# currentSens.net
KiCad netlist of a schematic drawn in EAGLE
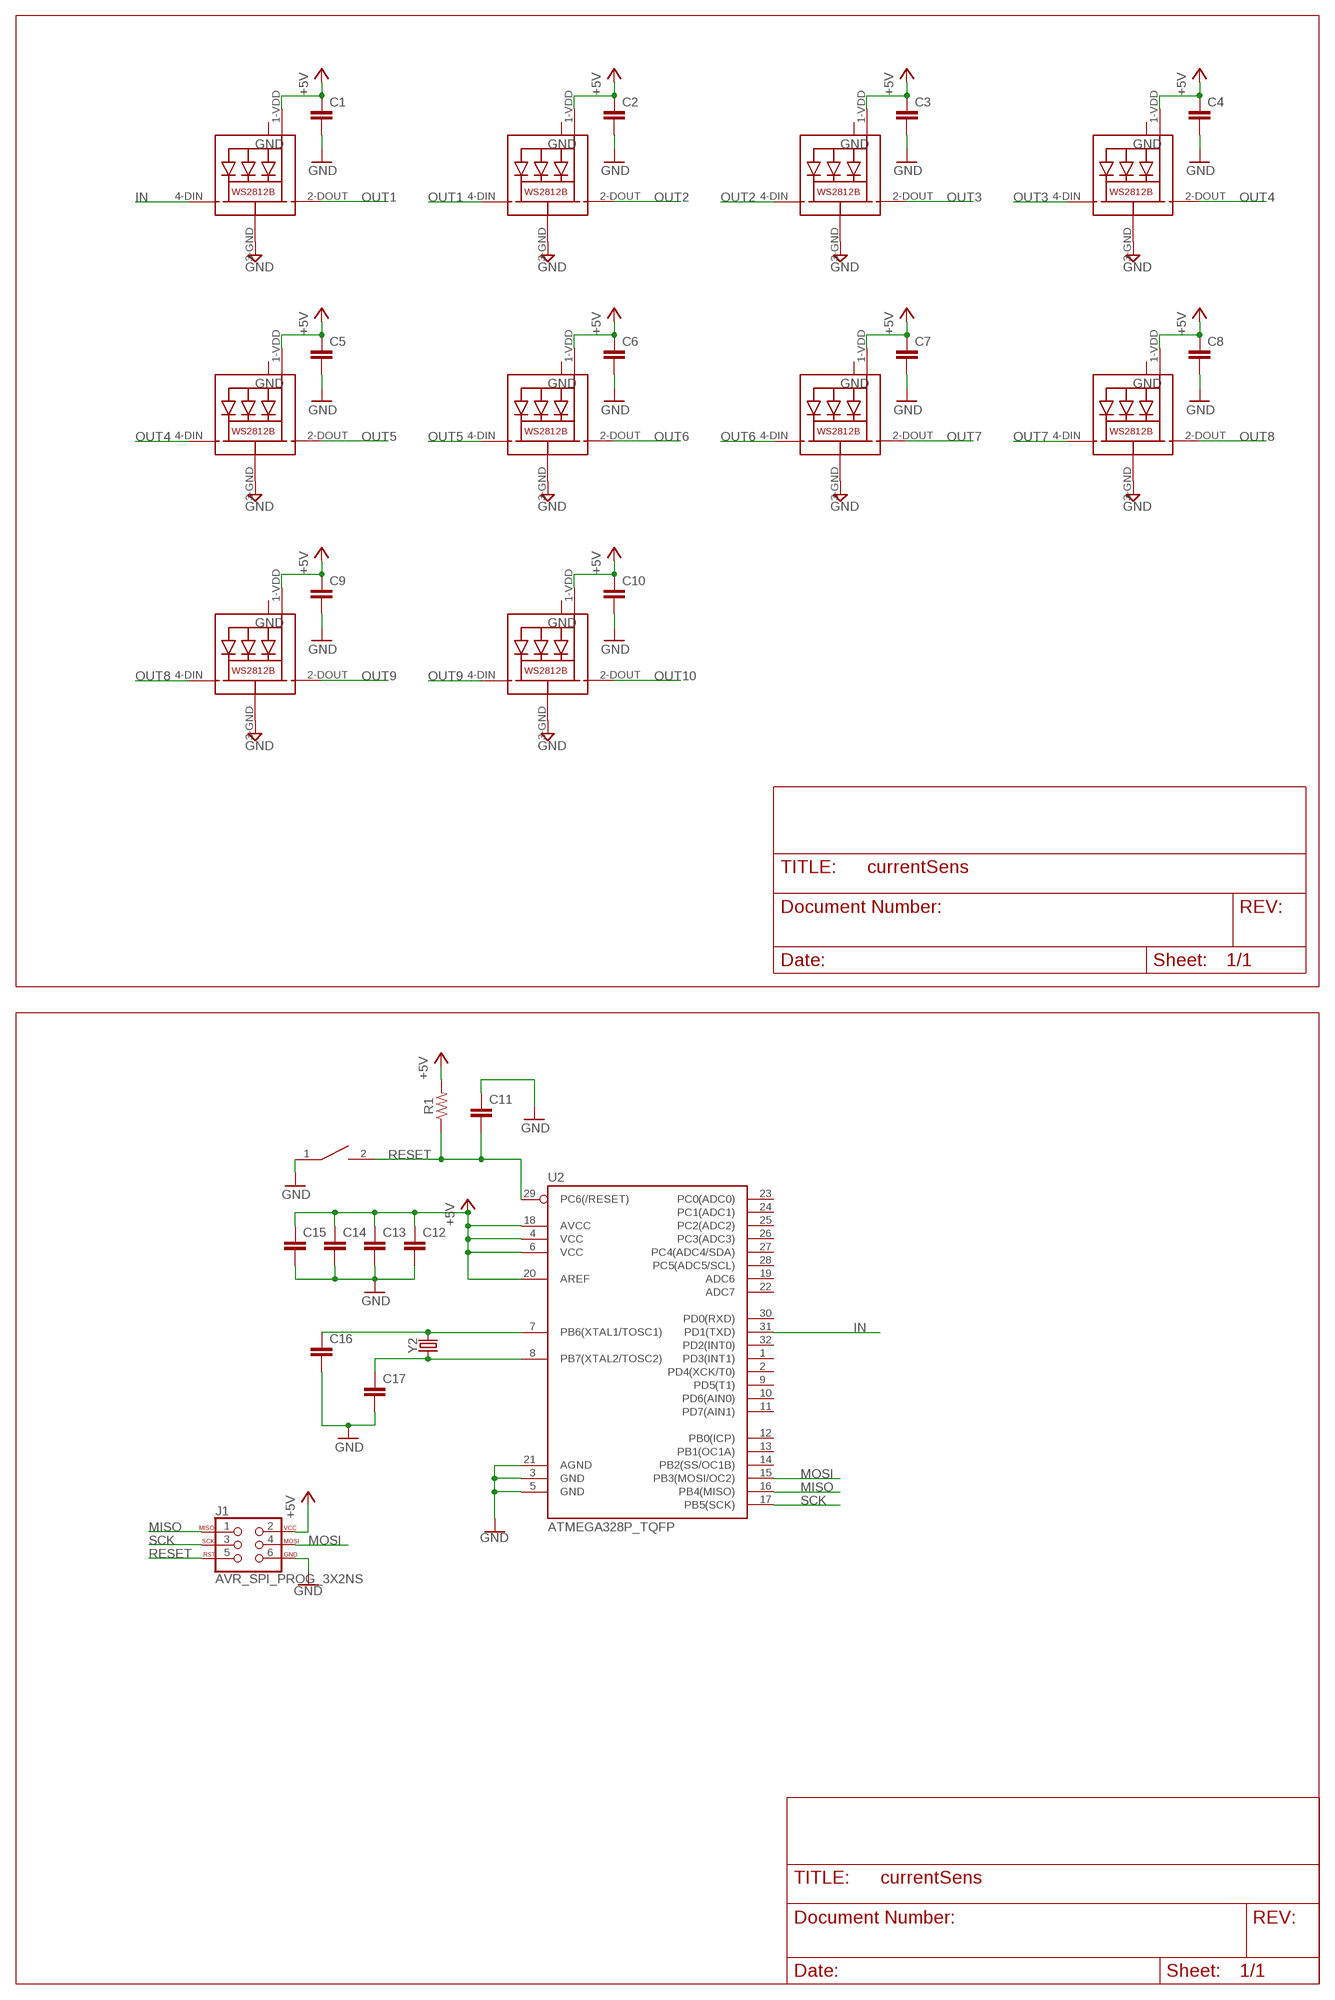
[diagram p0: schematic, sheet 1]

(export (version "E")
  (design (tool "Eeschema 10.0.6"))
  (components
    (comp (ref "BOOT")
      (value "SWITCH")
      (footprint "eagle-import:SW_2512")
      (libsource (lib "eagle-import") (part "SWITCH"))
    )
    (comp (ref "C1")
      (value "C-EUC0603")
      (footprint "eagle-import:C0603")
      (libsource (lib "eagle-import") (part "C-EUC0603"))
    )
    (comp (ref "C2")
      (value "C-EUC0603")
      (footprint "eagle-import:C0603")
      (libsource (lib "eagle-import") (part "C-EUC0603"))
    )
    (comp (ref "C3")
      (value "C-EUC0603")
      (footprint "eagle-import:C0603")
      (libsource (lib "eagle-import") (part "C-EUC0603"))
    )
    (comp (ref "C4")
      (value "C-EUC0603")
      (footprint "eagle-import:C0603")
      (libsource (lib "eagle-import") (part "C-EUC0603"))
    )
    (comp (ref "C5")
      (value "C-EUC0603")
      (footprint "eagle-import:C0603")
      (libsource (lib "eagle-import") (part "C-EUC0603"))
    )
    (comp (ref "C6")
      (value "C-EUC0603")
      (footprint "eagle-import:C0603")
      (libsource (lib "eagle-import") (part "C-EUC0603"))
    )
    (comp (ref "C7")
      (value "C-EUC0603")
      (footprint "eagle-import:C0603")
      (libsource (lib "eagle-import") (part "C-EUC0603"))
    )
    (comp (ref "C8")
      (value "C-EUC0603")
      (footprint "eagle-import:C0603")
      (libsource (lib "eagle-import") (part "C-EUC0603"))
    )
    (comp (ref "C9")
      (value "C-EUC0603")
      (footprint "eagle-import:C0603")
      (libsource (lib "eagle-import") (part "C-EUC0603"))
    )
    (comp (ref "C10")
      (value "C-EUC0603")
      (footprint "eagle-import:C0603")
      (libsource (lib "eagle-import") (part "C-EUC0603"))
    )
    (comp (ref "C11")
      (value "C-EUC0603")
      (footprint "eagle-import:C0603")
      (libsource (lib "eagle-import") (part "C-EUC0603"))
    )
    (comp (ref "C12")
      (value "C-EUC0603")
      (footprint "eagle-import:C0603")
      (libsource (lib "eagle-import") (part "C-EUC0603"))
    )
    (comp (ref "C13")
      (value "C-EUC0603")
      (footprint "eagle-import:C0603")
      (libsource (lib "eagle-import") (part "C-EUC0603"))
    )
    (comp (ref "C14")
      (value "C-EUC0603")
      (footprint "eagle-import:C0603")
      (libsource (lib "eagle-import") (part "C-EUC0603"))
    )
    (comp (ref "C15")
      (value "C-EUC0603")
      (footprint "eagle-import:C0603")
      (libsource (lib "eagle-import") (part "C-EUC0603"))
    )
    (comp (ref "C16")
      (value "C-EUC0603")
      (footprint "eagle-import:C0603")
      (libsource (lib "eagle-import") (part "C-EUC0603"))
    )
    (comp (ref "C17")
      (value "C-EUC0603")
      (footprint "eagle-import:C0603")
      (libsource (lib "eagle-import") (part "C-EUC0603"))
    )
    (comp (ref "J1")
      (value "AVR_SPI_PROG_3X2NS")
      (footprint "eagle-import:2X3-NS")
      (libsource (lib "eagle-import") (part "AVR_SPI_PROG_3X2NS"))
    )
    (comp (ref "LED1")
      (value "WS2812B5050")
      (footprint "eagle-import:WS2812B")
      (libsource (lib "eagle-import") (part "WS2812B5050"))
    )
    (comp (ref "LED2")
      (value "WS2812B5050")
      (footprint "eagle-import:WS2812B")
      (libsource (lib "eagle-import") (part "WS2812B5050"))
    )
    (comp (ref "LED3")
      (value "WS2812B5050")
      (footprint "eagle-import:WS2812B")
      (libsource (lib "eagle-import") (part "WS2812B5050"))
    )
    (comp (ref "LED4")
      (value "WS2812B5050")
      (footprint "eagle-import:WS2812B")
      (libsource (lib "eagle-import") (part "WS2812B5050"))
    )
    (comp (ref "LED5")
      (value "WS2812B5050")
      (footprint "eagle-import:WS2812B")
      (libsource (lib "eagle-import") (part "WS2812B5050"))
    )
    (comp (ref "LED6")
      (value "WS2812B5050")
      (footprint "eagle-import:WS2812B")
      (libsource (lib "eagle-import") (part "WS2812B5050"))
    )
    (comp (ref "LED7")
      (value "WS2812B5050")
      (footprint "eagle-import:WS2812B")
      (libsource (lib "eagle-import") (part "WS2812B5050"))
    )
    (comp (ref "LED8")
      (value "WS2812B5050")
      (footprint "eagle-import:WS2812B")
      (libsource (lib "eagle-import") (part "WS2812B5050"))
    )
    (comp (ref "LED9")
      (value "WS2812B5050")
      (footprint "eagle-import:WS2812B")
      (libsource (lib "eagle-import") (part "WS2812B5050"))
    )
    (comp (ref "LED10")
      (value "WS2812B5050")
      (footprint "eagle-import:WS2812B")
      (libsource (lib "eagle-import") (part "WS2812B5050"))
    )
    (comp (ref "R1")
      (value "RESISTOR0603")
      (footprint "eagle-import:0603")
      (libsource (lib "eagle-import") (part "RESISTOR0603"))
    )
    (comp (ref "U2")
      (value "ATMEGA328P_TQFP")
      (footprint "eagle-import:TQFP32-08")
      (libsource (lib "eagle-import") (part "ATMEGA328P_TQFP"))
    )
    (comp (ref "Y2")
      (value "CRYSTALPTH-HC49US")
      (footprint "eagle-import:HC49US")
      (libsource (lib "eagle-import") (part "CRYSTALPTH-HC49US"))
    )
  )
  (nets
    (net (code "1") (name "+5V") (class "Default")
      (node (ref "C1") (pin "1") (pinfunction "1_1") (pintype "passive"))
      (node (ref "C10") (pin "1") (pinfunction "1_1") (pintype "passive"))
      (node (ref "C12") (pin "1") (pinfunction "1_1") (pintype "passive"))
      (node (ref "C13") (pin "1") (pinfunction "1_1") (pintype "passive"))
      (node (ref "C14") (pin "1") (pinfunction "1_1") (pintype "passive"))
      (node (ref "C15") (pin "1") (pinfunction "1_1") (pintype "passive"))
      (node (ref "C2") (pin "1") (pinfunction "1_1") (pintype "passive"))
      (node (ref "C3") (pin "1") (pinfunction "1_1") (pintype "passive"))
      (node (ref "C4") (pin "1") (pinfunction "1_1") (pintype "passive"))
      (node (ref "C5") (pin "1") (pinfunction "1_1") (pintype "passive"))
      (node (ref "C6") (pin "1") (pinfunction "1_1") (pintype "passive"))
      (node (ref "C7") (pin "1") (pinfunction "1_1") (pintype "passive"))
      (node (ref "C8") (pin "1") (pinfunction "1_1") (pintype "passive"))
      (node (ref "C9") (pin "1") (pinfunction "1_1") (pintype "passive"))
      (node (ref "J1") (pin "2") (pinfunction "2_2") (pintype "passive"))
      (node (ref "LED1") (pin "1-VDD") (pinfunction "VDD_1-VDD") (pintype "power_in"))
      (node (ref "LED10") (pin "1-VDD") (pinfunction "VDD_1-VDD") (pintype "power_in"))
      (node (ref "LED2") (pin "1-VDD") (pinfunction "VDD_1-VDD") (pintype "power_in"))
      (node (ref "LED3") (pin "1-VDD") (pinfunction "VDD_1-VDD") (pintype "power_in"))
      (node (ref "LED4") (pin "1-VDD") (pinfunction "VDD_1-VDD") (pintype "power_in"))
      (node (ref "LED5") (pin "1-VDD") (pinfunction "VDD_1-VDD") (pintype "power_in"))
      (node (ref "LED6") (pin "1-VDD") (pinfunction "VDD_1-VDD") (pintype "power_in"))
      (node (ref "LED7") (pin "1-VDD") (pinfunction "VDD_1-VDD") (pintype "power_in"))
      (node (ref "LED8") (pin "1-VDD") (pinfunction "VDD_1-VDD") (pintype "power_in"))
      (node (ref "LED9") (pin "1-VDD") (pinfunction "VDD_1-VDD") (pintype "power_in"))
      (node (ref "R1") (pin "2") (pinfunction "2_2") (pintype "passive"))
      (node (ref "U2") (pin "18") (pinfunction "AVCC_18") (pintype "bidirectional"))
      (node (ref "U2") (pin "20") (pinfunction "AREF_20") (pintype "bidirectional"))
      (node (ref "U2") (pin "4") (pinfunction "VCC_4") (pintype "bidirectional"))
      (node (ref "U2") (pin "6") (pinfunction "VCC_6") (pintype "bidirectional"))
    )
    (net (code "2") (name "/IN") (class "Default")
      (node (ref "LED1") (pin "4-DIN") (pinfunction "DI_4-DIN") (pintype "input"))
      (node (ref "U2") (pin "31") (pinfunction "PD1(TXD)_31") (pintype "bidirectional"))
    )
    (net (code "3") (name "/MISO") (class "Default")
      (node (ref "J1") (pin "1") (pinfunction "1_1") (pintype "passive"))
      (node (ref "U2") (pin "16") (pinfunction "PB4(MISO)_16") (pintype "bidirectional"))
    )
    (net (code "4") (name "/MOSI") (class "Default")
      (node (ref "J1") (pin "4") (pinfunction "4_4") (pintype "passive"))
      (node (ref "U2") (pin "15") (pinfunction "PB3(MOSI/OC2)_15") (pintype "bidirectional"))
    )
    (net (code "5") (name "/OUT1") (class "Default")
      (node (ref "LED1") (pin "2-DOUT") (pinfunction "DO_2-DOUT") (pintype "output"))
      (node (ref "LED2") (pin "4-DIN") (pinfunction "DI_4-DIN") (pintype "input"))
    )
    (net (code "6") (name "/OUT2") (class "Default")
      (node (ref "LED2") (pin "2-DOUT") (pinfunction "DO_2-DOUT") (pintype "output"))
      (node (ref "LED3") (pin "4-DIN") (pinfunction "DI_4-DIN") (pintype "input"))
    )
    (net (code "7") (name "/OUT3") (class "Default")
      (node (ref "LED3") (pin "2-DOUT") (pinfunction "DO_2-DOUT") (pintype "output"))
      (node (ref "LED4") (pin "4-DIN") (pinfunction "DI_4-DIN") (pintype "input"))
    )
    (net (code "8") (name "/OUT4") (class "Default")
      (node (ref "LED4") (pin "2-DOUT") (pinfunction "DO_2-DOUT") (pintype "output"))
      (node (ref "LED5") (pin "4-DIN") (pinfunction "DI_4-DIN") (pintype "input"))
    )
    (net (code "9") (name "/OUT5") (class "Default")
      (node (ref "LED5") (pin "2-DOUT") (pinfunction "DO_2-DOUT") (pintype "output"))
      (node (ref "LED6") (pin "4-DIN") (pinfunction "DI_4-DIN") (pintype "input"))
    )
    (net (code "10") (name "/OUT6") (class "Default")
      (node (ref "LED6") (pin "2-DOUT") (pinfunction "DO_2-DOUT") (pintype "output"))
      (node (ref "LED7") (pin "4-DIN") (pinfunction "DI_4-DIN") (pintype "input"))
    )
    (net (code "11") (name "/OUT7") (class "Default")
      (node (ref "LED7") (pin "2-DOUT") (pinfunction "DO_2-DOUT") (pintype "output"))
      (node (ref "LED8") (pin "4-DIN") (pinfunction "DI_4-DIN") (pintype "input"))
    )
    (net (code "12") (name "/OUT8") (class "Default")
      (node (ref "LED8") (pin "2-DOUT") (pinfunction "DO_2-DOUT") (pintype "output"))
      (node (ref "LED9") (pin "4-DIN") (pinfunction "DI_4-DIN") (pintype "input"))
    )
    (net (code "13") (name "/OUT9") (class "Default")
      (node (ref "LED10") (pin "4-DIN") (pinfunction "DI_4-DIN") (pintype "input"))
      (node (ref "LED9") (pin "2-DOUT") (pinfunction "DO_2-DOUT") (pintype "output"))
    )
    (net (code "14") (name "/OUT10") (class "Default")
      (node (ref "LED10") (pin "2-DOUT") (pinfunction "DO_2-DOUT") (pintype "output"))
    )
    (net (code "15") (name "/RESET") (class "Default")
      (node (ref "BOOT") (pin "2") (pinfunction "P$2_2") (pintype "bidirectional"))
      (node (ref "C11") (pin "2") (pinfunction "2_2") (pintype "passive"))
      (node (ref "J1") (pin "5") (pinfunction "5_5") (pintype "passive"))
      (node (ref "R1") (pin "1") (pinfunction "1_1") (pintype "passive"))
      (node (ref "U2") (pin "29") (pinfunction "PC6(/RESET)_29") (pintype "bidirectional"))
    )
    (net (code "16") (name "/SCK") (class "Default")
      (node (ref "J1") (pin "3") (pinfunction "3_3") (pintype "passive"))
      (node (ref "U2") (pin "17") (pinfunction "PB5(SCK)_17") (pintype "bidirectional"))
    )
    (net (code "17") (name "GND") (class "Default")
      (node (ref "BOOT") (pin "1") (pinfunction "P$1_1") (pintype "bidirectional"))
      (node (ref "C1") (pin "2") (pinfunction "2_2") (pintype "passive"))
      (node (ref "C10") (pin "2") (pinfunction "2_2") (pintype "passive"))
      (node (ref "C11") (pin "1") (pinfunction "1_1") (pintype "passive"))
      (node (ref "C12") (pin "2") (pinfunction "2_2") (pintype "passive"))
      (node (ref "C13") (pin "2") (pinfunction "2_2") (pintype "passive"))
      (node (ref "C14") (pin "2") (pinfunction "2_2") (pintype "passive"))
      (node (ref "C15") (pin "2") (pinfunction "2_2") (pintype "passive"))
      (node (ref "C16") (pin "2") (pinfunction "2_2") (pintype "passive"))
      (node (ref "C17") (pin "2") (pinfunction "2_2") (pintype "passive"))
      (node (ref "C2") (pin "2") (pinfunction "2_2") (pintype "passive"))
      (node (ref "C3") (pin "2") (pinfunction "2_2") (pintype "passive"))
      (node (ref "C4") (pin "2") (pinfunction "2_2") (pintype "passive"))
      (node (ref "C5") (pin "2") (pinfunction "2_2") (pintype "passive"))
      (node (ref "C6") (pin "2") (pinfunction "2_2") (pintype "passive"))
      (node (ref "C7") (pin "2") (pinfunction "2_2") (pintype "passive"))
      (node (ref "C8") (pin "2") (pinfunction "2_2") (pintype "passive"))
      (node (ref "C9") (pin "2") (pinfunction "2_2") (pintype "passive"))
      (node (ref "J1") (pin "6") (pinfunction "6_6") (pintype "passive"))
      (node (ref "LED1") (pin "3-GND") (pinfunction "GND_3-GND") (pintype "power_in"))
      (node (ref "LED10") (pin "3-GND") (pinfunction "GND_3-GND") (pintype "power_in"))
      (node (ref "LED2") (pin "3-GND") (pinfunction "GND_3-GND") (pintype "power_in"))
      (node (ref "LED3") (pin "3-GND") (pinfunction "GND_3-GND") (pintype "power_in"))
      (node (ref "LED4") (pin "3-GND") (pinfunction "GND_3-GND") (pintype "power_in"))
      (node (ref "LED5") (pin "3-GND") (pinfunction "GND_3-GND") (pintype "power_in"))
      (node (ref "LED6") (pin "3-GND") (pinfunction "GND_3-GND") (pintype "power_in"))
      (node (ref "LED7") (pin "3-GND") (pinfunction "GND_3-GND") (pintype "power_in"))
      (node (ref "LED8") (pin "3-GND") (pinfunction "GND_3-GND") (pintype "power_in"))
      (node (ref "LED9") (pin "3-GND") (pinfunction "GND_3-GND") (pintype "power_in"))
      (node (ref "U2") (pin "21") (pinfunction "AGND_21") (pintype "bidirectional"))
      (node (ref "U2") (pin "3") (pinfunction "GND_3") (pintype "bidirectional"))
      (node (ref "U2") (pin "5") (pinfunction "GND_5") (pintype "bidirectional"))
    )
    (net (code "18") (name "Net-(U2-PB6(XTAL1{slash}TOSC1))") (class "Default")
      (node (ref "C16") (pin "1") (pinfunction "1_1") (pintype "passive"))
      (node (ref "U2") (pin "7") (pinfunction "PB6(XTAL1/TOSC1)_7") (pintype "bidirectional"))
      (node (ref "Y2") (pin "2") (pinfunction "2_2") (pintype "passive"))
    )
    (net (code "19") (name "Net-(U2-PB7(XTAL2{slash}TOSC2))") (class "Default")
      (node (ref "C17") (pin "1") (pinfunction "1_1") (pintype "passive"))
      (node (ref "U2") (pin "8") (pinfunction "PB7(XTAL2/TOSC2)_8") (pintype "bidirectional"))
      (node (ref "Y2") (pin "1") (pinfunction "1_1") (pintype "passive"))
    )
    (net (code "20") (name "unconnected-(U2-ADC6-Pad19)") (class "Default")
      (node (ref "U2") (pin "19") (pinfunction "ADC6_19") (pintype "bidirectional"))
    )
    (net (code "21") (name "unconnected-(U2-ADC7-Pad22)") (class "Default")
      (node (ref "U2") (pin "22") (pinfunction "ADC7_22") (pintype "bidirectional"))
    )
    (net (code "22") (name "unconnected-(U2-PB0(ICP)-Pad12)") (class "Default")
      (node (ref "U2") (pin "12") (pinfunction "PB0(ICP)_12") (pintype "bidirectional"))
    )
    (net (code "23") (name "unconnected-(U2-PB1(OC1A)-Pad13)") (class "Default")
      (node (ref "U2") (pin "13") (pinfunction "PB1(OC1A)_13") (pintype "bidirectional"))
    )
    (net (code "24") (name "unconnected-(U2-PB2(SS{slash}OC1B)-Pad14)") (class "Default")
      (node (ref "U2") (pin "14") (pinfunction "PB2(SS/OC1B)_14") (pintype "bidirectional"))
    )
    (net (code "25") (name "unconnected-(U2-PC0(ADC0)-Pad23)") (class "Default")
      (node (ref "U2") (pin "23") (pinfunction "PC0(ADC0)_23") (pintype "bidirectional"))
    )
    (net (code "26") (name "unconnected-(U2-PC1(ADC1)-Pad24)") (class "Default")
      (node (ref "U2") (pin "24") (pinfunction "PC1(ADC1)_24") (pintype "bidirectional"))
    )
    (net (code "27") (name "unconnected-(U2-PC2(ADC2)-Pad25)") (class "Default")
      (node (ref "U2") (pin "25") (pinfunction "PC2(ADC2)_25") (pintype "bidirectional"))
    )
    (net (code "28") (name "unconnected-(U2-PC3(ADC3)-Pad26)") (class "Default")
      (node (ref "U2") (pin "26") (pinfunction "PC3(ADC3)_26") (pintype "bidirectional"))
    )
    (net (code "29") (name "unconnected-(U2-PC4(ADC4{slash}SDA)-Pad27)") (class "Default")
      (node (ref "U2") (pin "27") (pinfunction "PC4(ADC4/SDA)_27") (pintype "bidirectional"))
    )
    (net (code "30") (name "unconnected-(U2-PC5(ADC5{slash}SCL)-Pad28)") (class "Default")
      (node (ref "U2") (pin "28") (pinfunction "PC5(ADC5/SCL)_28") (pintype "bidirectional"))
    )
    (net (code "31") (name "unconnected-(U2-PD0(RXD)-Pad30)") (class "Default")
      (node (ref "U2") (pin "30") (pinfunction "PD0(RXD)_30") (pintype "bidirectional"))
    )
    (net (code "32") (name "unconnected-(U2-PD2(INT0)-Pad32)") (class "Default")
      (node (ref "U2") (pin "32") (pinfunction "PD2(INT0)_32") (pintype "bidirectional"))
    )
    (net (code "33") (name "unconnected-(U2-PD3(INT1)-Pad1)") (class "Default")
      (node (ref "U2") (pin "1") (pinfunction "PD3(INT1)_1") (pintype "bidirectional"))
    )
    (net (code "34") (name "unconnected-(U2-PD4(XCK{slash}T0)-Pad2)") (class "Default")
      (node (ref "U2") (pin "2") (pinfunction "PD4(XCK/T0)_2") (pintype "bidirectional"))
    )
    (net (code "35") (name "unconnected-(U2-PD5(T1)-Pad9)") (class "Default")
      (node (ref "U2") (pin "9") (pinfunction "PD5(T1)_9") (pintype "bidirectional"))
    )
    (net (code "36") (name "unconnected-(U2-PD6(AIN0)-Pad10)") (class "Default")
      (node (ref "U2") (pin "10") (pinfunction "PD6(AIN0)_10") (pintype "bidirectional"))
    )
    (net (code "37") (name "unconnected-(U2-PD7(AIN1)-Pad11)") (class "Default")
      (node (ref "U2") (pin "11") (pinfunction "PD7(AIN1)_11") (pintype "bidirectional"))
    )
  )
)
